# Raspi-TPUART_v1_3.net
KiCad netlist of a schematic drawn in EAGLE
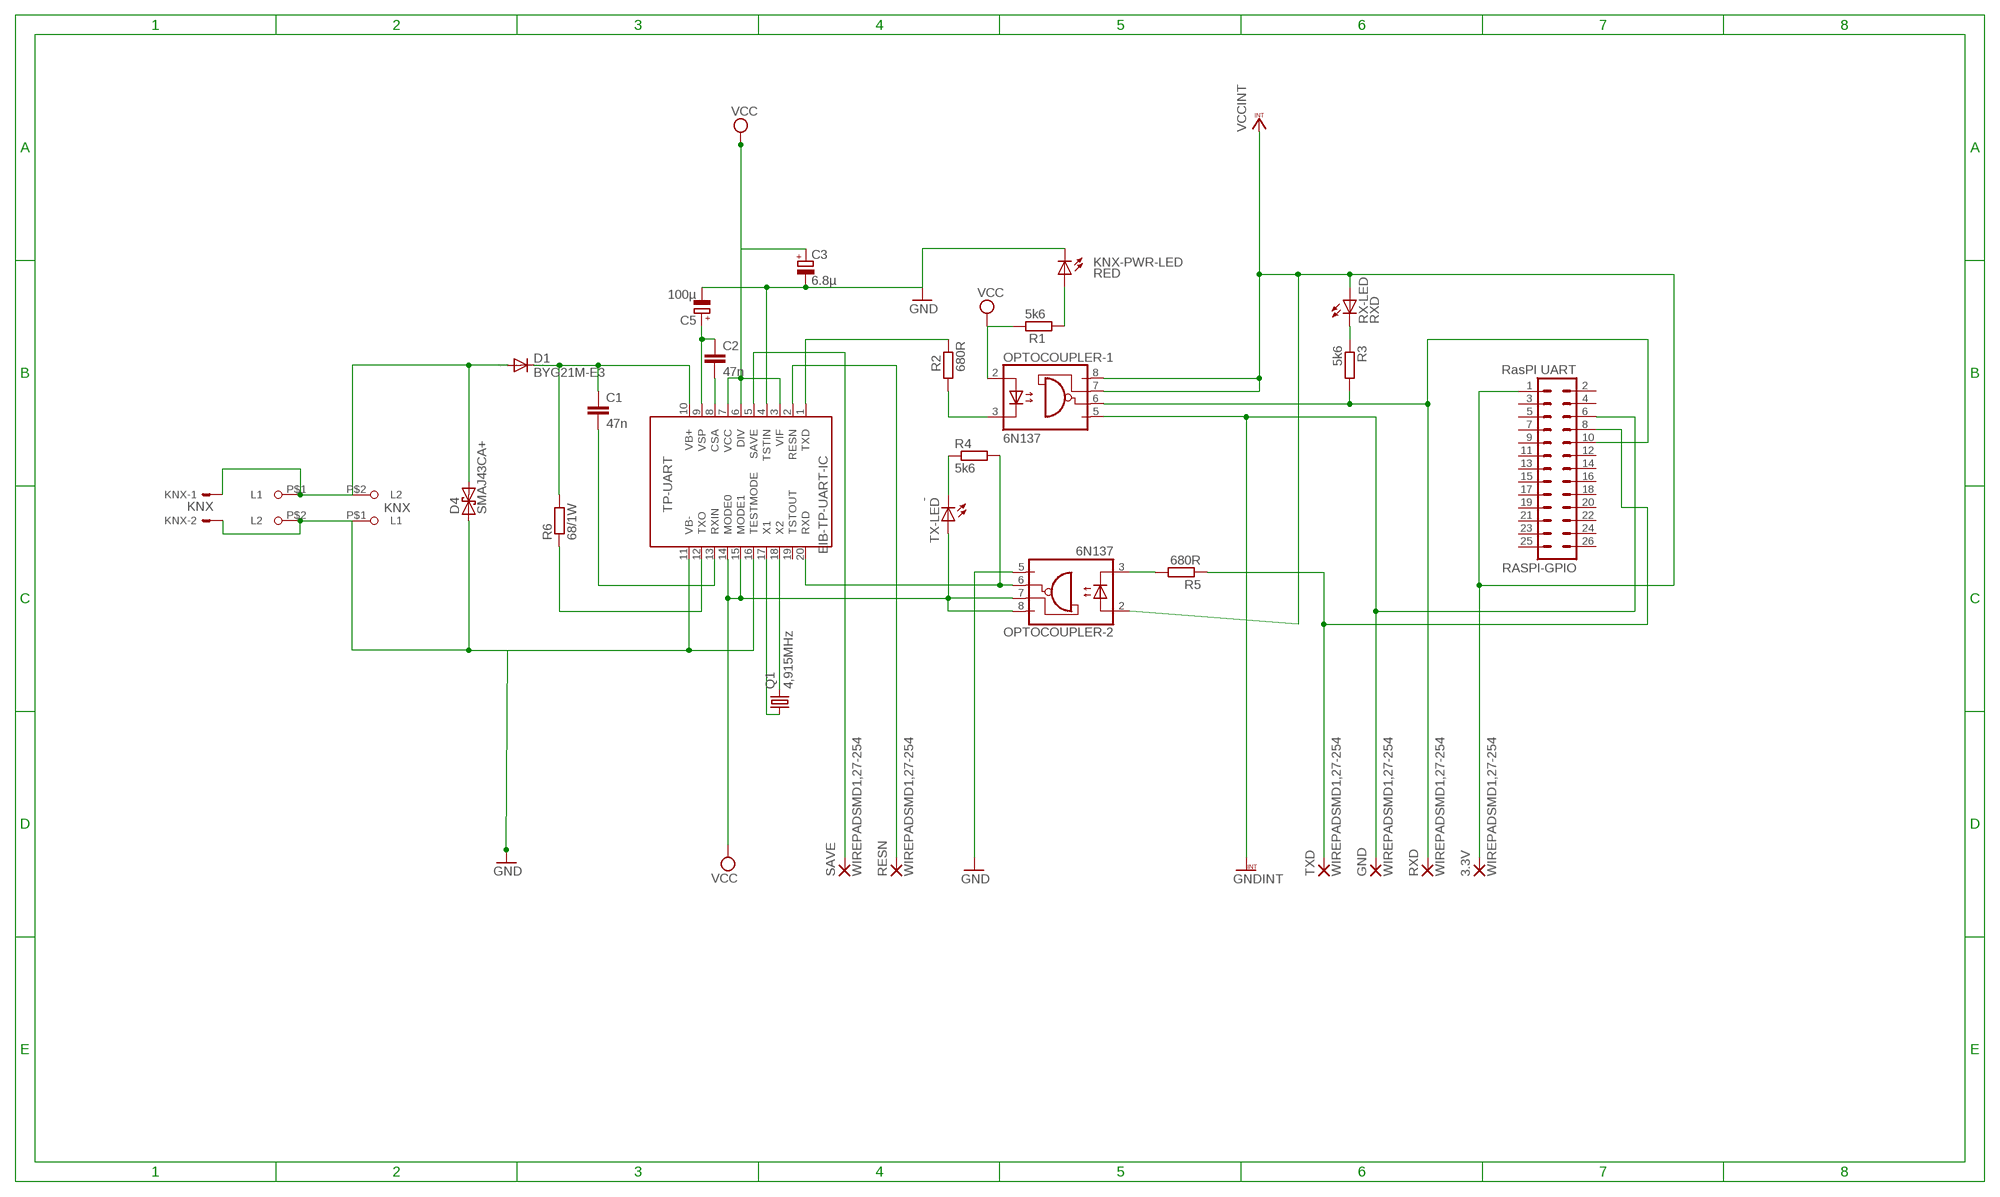
[diagram p0: schematic, sheet 1]

(export (version "E")
  (design (tool "Eeschema 10.0.6"))
  (components
    (comp (ref "3.3V")
      (value "WIREPADSMD1,27-254")
      (footprint "eagle-import:SMD1,27-2,54")
      (libsource (lib "eagle-import") (part "WIREPADSMD1,27-254"))
    )
    (comp (ref "C1")
      (value "47n")
      (footprint "eagle-import:C1206")
      (libsource (lib "eagle-import") (part "C-EUC1206"))
    )
    (comp (ref "C2")
      (value "47n")
      (footprint "eagle-import:C1206")
      (libsource (lib "eagle-import") (part "C-EUC1206"))
    )
    (comp (ref "C3")
      (value "6.8µ")
      (footprint "eagle-import:D_7343-31R")
      (libsource (lib "eagle-import") (part "CPOL-EUD/7343-31R"))
    )
    (comp (ref "C5")
      (value "100µ")
      (footprint "eagle-import:D_7343-31R")
      (libsource (lib "eagle-import") (part "CPOL-EUD/7343-31R"))
    )
    (comp (ref "D1")
      (value "BYG21M-E3")
      (footprint "eagle-import:SMB")
      (libsource (lib "eagle-import") (part "ES2D"))
    )
    (comp (ref "D4")
      (value "SMAJ43CA+")
      (footprint "eagle-import:DO214AA")
      (libsource (lib "eagle-import") (part "BZW04XXB"))
    )
    (comp (ref "EIB-TP-UART-IC")
      (value "TP-UART")
      (footprint "eagle-import:SOIC20")
      (libsource (lib "eagle-import") (part "TP-UART"))
    )
    (comp (ref "GND")
      (value "WIREPADSMD1,27-254")
      (footprint "eagle-import:SMD1,27-2,54")
      (libsource (lib "eagle-import") (part "WIREPADSMD1,27-254"))
    )
    (comp (ref "KNX")
      (value "KNX")
      (footprint "eagle-import:22-23-2021")
      (fields (field (name "MF") "MOLEX") (field (name "MPN") "22-23-2021"))
      (libsource (lib "eagle-import") (part "22-23-2021"))
    )
    (comp (ref "KNX-PWR-LED")
      (value "RED")
      (footprint "eagle-import:KA-3528ASYC")
      (libsource (lib "eagle-import") (part "LEDKA-3528ASYC"))
    )
    (comp (ref "KNX_WAGO_243")
      (value "243-211")
      (footprint "eagle-import:243-211")
      (libsource (lib "eagle-import") (part "243-211"))
    )
    (comp (ref "OPTOCOUPLER-1")
      (value "6N137")
      (footprint "eagle-import:DIL8-SMD")
      (libsource (lib "eagle-import") (part "6N137"))
    )
    (comp (ref "OPTOCOUPLER-2")
      (value "6N137")
      (footprint "eagle-import:DIL8-SMD")
      (libsource (lib "eagle-import") (part "6N137"))
    )
    (comp (ref "Q1")
      (value "4,915MHz")
      (footprint "eagle-import:HC49UP")
      (libsource (lib "eagle-import") (part "CRYSTALHC49UP"))
    )
    (comp (ref "R1")
      (value "5k6")
      (footprint "eagle-import:M1206")
      (libsource (lib "eagle-import") (part "R-EU_M1206"))
    )
    (comp (ref "R2")
      (value "680R")
      (footprint "eagle-import:M1206")
      (libsource (lib "eagle-import") (part "R-EU_M1206"))
    )
    (comp (ref "R3")
      (value "5k6")
      (footprint "eagle-import:M1206")
      (libsource (lib "eagle-import") (part "R-EU_M1206"))
    )
    (comp (ref "R4")
      (value "5k6")
      (footprint "eagle-import:M1206")
      (libsource (lib "eagle-import") (part "R-EU_M1206"))
    )
    (comp (ref "R5")
      (value "680R")
      (footprint "eagle-import:M1206")
      (libsource (lib "eagle-import") (part "R-EU_M1206"))
    )
    (comp (ref "R6")
      (value "68/1W")
      (footprint "eagle-import:R2512")
      (libsource (lib "eagle-import") (part "R-EU_R2512"))
    )
    (comp (ref "RASPI-GPIO")
      (value "RasPI UART")
      (footprint "eagle-import:MA13-2")
      (libsource (lib "eagle-import") (part "MA13-2"))
    )
    (comp (ref "RESN")
      (value "WIREPADSMD1,27-254")
      (footprint "eagle-import:SMD1,27-2,54")
      (libsource (lib "eagle-import") (part "WIREPADSMD1,27-254"))
    )
    (comp (ref "RX-LED")
      (value "RXD")
      (footprint "eagle-import:KA-3528ASYC")
      (libsource (lib "eagle-import") (part "LEDKA-3528ASYC"))
    )
    (comp (ref "RXD")
      (value "WIREPADSMD1,27-254")
      (footprint "eagle-import:SMD1,27-2,54")
      (libsource (lib "eagle-import") (part "WIREPADSMD1,27-254"))
    )
    (comp (ref "SAVE")
      (value "WIREPADSMD1,27-254")
      (footprint "eagle-import:SMD1,27-2,54")
      (libsource (lib "eagle-import") (part "WIREPADSMD1,27-254"))
    )
    (comp (ref "TX-LED")
      (value "-")
      (footprint "eagle-import:KA-3528ASYC")
      (libsource (lib "eagle-import") (part "LEDKA-3528ASYC"))
    )
    (comp (ref "TXD")
      (value "WIREPADSMD1,27-254")
      (footprint "eagle-import:SMD1,27-2,54")
      (libsource (lib "eagle-import") (part "WIREPADSMD1,27-254"))
    )
    (comp (ref "U$1")
      (value "243-211")
      (footprint "eagle-import:243-211")
      (libsource (lib "eagle-import") (part "243-211"))
    )
  )
  (nets
    (net (code "1") (name "GND") (class "Default")
      (node (ref "C3") (pin "-") (pinfunction "-_-") (pintype "passive"))
      (node (ref "C5") (pin "-") (pinfunction "-_-") (pintype "passive"))
      (node (ref "D4") (pin "A") (pinfunction "1_A") (pintype "passive"))
      (node (ref "EIB-TP-UART-IC") (pin "11") (pinfunction "VB-_11") (pintype "passive"))
      (node (ref "EIB-TP-UART-IC") (pin "16") (pinfunction "TESTMODE_16") (pintype "input"))
      (node (ref "EIB-TP-UART-IC") (pin "4") (pinfunction "TSTIN_4") (pintype "bidirectional"))
      (node (ref "KNX") (pin "2") (pinfunction "S_2") (pintype "passive"))
      (node (ref "KNX-PWR-LED") (pin "C") (pinfunction "C_C") (pintype "passive"))
      (node (ref "KNX_WAGO_243") (pin "P$1") (pinfunction "L1_P$1") (pintype "bidirectional"))
      (node (ref "OPTOCOUPLER-2") (pin "5") (pinfunction "GND_5") (pintype "passive"))
      (node (ref "U$1") (pin "P$2") (pinfunction "L2_P$2") (pintype "bidirectional"))
    )
    (net (code "2") (name "GNDINT") (class "Default")
      (node (ref "GND") (pin "1") (pinfunction "P_1") (pintype "passive"))
      (node (ref "OPTOCOUPLER-1") (pin "5") (pinfunction "GND_5") (pintype "passive"))
      (node (ref "RASPI-GPIO") (pin "6") (pinfunction "6_6") (pintype "passive"))
    )
    (net (code "3") (name "Net-(D4-2)") (class "Default")
      (node (ref "D1") (pin "A") (pinfunction "A_A") (pintype "passive"))
      (node (ref "D4") (pin "C") (pinfunction "2_C") (pintype "passive"))
      (node (ref "KNX") (pin "1") (pinfunction "S_1") (pintype "passive"))
      (node (ref "KNX_WAGO_243") (pin "P$2") (pinfunction "L2_P$2") (pintype "bidirectional"))
      (node (ref "U$1") (pin "P$1") (pinfunction "L1_P$1") (pintype "bidirectional"))
    )
    (net (code "4") (name "Net-(EIB-TP-UART-IC-CSA)") (class "Default")
      (node (ref "C2") (pin "2") (pinfunction "2_2") (pintype "passive"))
      (node (ref "EIB-TP-UART-IC") (pin "8") (pinfunction "CSA_8") (pintype "passive"))
    )
    (net (code "5") (name "Net-(EIB-TP-UART-IC-RESN)") (class "Default")
      (node (ref "EIB-TP-UART-IC") (pin "2") (pinfunction "RESN_2") (pintype "bidirectional"))
      (node (ref "RESN") (pin "1") (pinfunction "P_1") (pintype "passive"))
    )
    (net (code "6") (name "Net-(EIB-TP-UART-IC-RXD)") (class "Default")
      (node (ref "EIB-TP-UART-IC") (pin "20") (pinfunction "RXD_20") (pintype "input"))
      (node (ref "OPTOCOUPLER-2") (pin "6") (pinfunction "VO_6") (pintype "passive"))
      (node (ref "R4") (pin "2") (pinfunction "2_2") (pintype "passive"))
    )
    (net (code "7") (name "Net-(EIB-TP-UART-IC-RXIN)") (class "Default")
      (node (ref "C1") (pin "2") (pinfunction "2_2") (pintype "passive"))
      (node (ref "EIB-TP-UART-IC") (pin "13") (pinfunction "RXIN_13") (pintype "input"))
    )
    (net (code "8") (name "Net-(EIB-TP-UART-IC-SAVE)") (class "Default")
      (node (ref "EIB-TP-UART-IC") (pin "5") (pinfunction "SAVE_5") (pintype "open_collector"))
      (node (ref "SAVE") (pin "1") (pinfunction "P_1") (pintype "passive"))
    )
    (net (code "9") (name "Net-(EIB-TP-UART-IC-TXD)") (class "Default")
      (node (ref "EIB-TP-UART-IC") (pin "1") (pinfunction "TXD_1") (pintype "output"))
      (node (ref "R2") (pin "2") (pinfunction "2_2") (pintype "passive"))
    )
    (net (code "10") (name "Net-(EIB-TP-UART-IC-TXO)") (class "Default")
      (node (ref "EIB-TP-UART-IC") (pin "12") (pinfunction "TXO_12") (pintype "output"))
      (node (ref "R6") (pin "1") (pinfunction "1_1") (pintype "passive"))
    )
    (net (code "11") (name "Net-(EIB-TP-UART-IC-VB+)") (class "Default")
      (node (ref "C1") (pin "1") (pinfunction "1_1") (pintype "passive"))
      (node (ref "D1") (pin "C") (pinfunction "C_C") (pintype "passive"))
      (node (ref "EIB-TP-UART-IC") (pin "10") (pinfunction "VB+_10") (pintype "passive"))
      (node (ref "R6") (pin "2") (pinfunction "2_2") (pintype "passive"))
    )
    (net (code "12") (name "Net-(EIB-TP-UART-IC-VSP)") (class "Default")
      (node (ref "C2") (pin "1") (pinfunction "1_1") (pintype "passive"))
      (node (ref "C5") (pin "+") (pinfunction "+_+") (pintype "passive"))
      (node (ref "EIB-TP-UART-IC") (pin "9") (pinfunction "VSP_9") (pintype "passive"))
    )
    (net (code "13") (name "Net-(EIB-TP-UART-IC-X1)") (class "Default")
      (node (ref "EIB-TP-UART-IC") (pin "17") (pinfunction "X1_17") (pintype "passive"))
      (node (ref "Q1") (pin "1") (pinfunction "1_1") (pintype "passive"))
    )
    (net (code "14") (name "Net-(EIB-TP-UART-IC-X2)") (class "Default")
      (node (ref "EIB-TP-UART-IC") (pin "18") (pinfunction "X2_18") (pintype "passive"))
      (node (ref "Q1") (pin "2") (pinfunction "2_2") (pintype "passive"))
    )
    (net (code "15") (name "Net-(KNX-PWR-LED-PadA)") (class "Default")
      (node (ref "KNX-PWR-LED") (pin "A") (pinfunction "A_A") (pintype "passive"))
      (node (ref "R1") (pin "1") (pinfunction "1_1") (pintype "passive"))
    )
    (net (code "16") (name "Net-(OPTOCOUPLER-1-C)") (class "Default")
      (node (ref "OPTOCOUPLER-1") (pin "3") (pinfunction "C_3") (pintype "passive"))
      (node (ref "R2") (pin "1") (pinfunction "1_1") (pintype "passive"))
    )
    (net (code "17") (name "Net-(OPTOCOUPLER-1-VO)") (class "Default")
      (node (ref "OPTOCOUPLER-1") (pin "6") (pinfunction "VO_6") (pintype "passive"))
      (node (ref "R3") (pin "2") (pinfunction "2_2") (pintype "passive"))
      (node (ref "RASPI-GPIO") (pin "10") (pinfunction "10_10") (pintype "passive"))
      (node (ref "RXD") (pin "1") (pinfunction "P_1") (pintype "passive"))
    )
    (net (code "18") (name "Net-(OPTOCOUPLER-2-C)") (class "Default")
      (node (ref "OPTOCOUPLER-2") (pin "3") (pinfunction "C_3") (pintype "passive"))
      (node (ref "R5") (pin "2") (pinfunction "2_2") (pintype "passive"))
    )
    (net (code "19") (name "Net-(R3-Pad1)") (class "Default")
      (node (ref "R3") (pin "1") (pinfunction "1_1") (pintype "passive"))
      (node (ref "RX-LED") (pin "C") (pinfunction "C_C") (pintype "passive"))
    )
    (net (code "20") (name "Net-(R4-Pad1)") (class "Default")
      (node (ref "R4") (pin "1") (pinfunction "1_1") (pintype "passive"))
      (node (ref "TX-LED") (pin "C") (pinfunction "C_C") (pintype "passive"))
    )
    (net (code "21") (name "Net-(TXD-P)") (class "Default")
      (node (ref "R5") (pin "1") (pinfunction "1_1") (pintype "passive"))
      (node (ref "RASPI-GPIO") (pin "8") (pinfunction "8_8") (pintype "passive"))
      (node (ref "TXD") (pin "1") (pinfunction "P_1") (pintype "passive"))
    )
    (net (code "22") (name "VCC") (class "Default")
      (node (ref "C3") (pin "+") (pinfunction "+_+") (pintype "passive"))
      (node (ref "EIB-TP-UART-IC") (pin "14") (pinfunction "MODE0_14") (pintype "input"))
      (node (ref "EIB-TP-UART-IC") (pin "15") (pinfunction "MODE1_15") (pintype "input"))
      (node (ref "EIB-TP-UART-IC") (pin "3") (pinfunction "VIF_3") (pintype "input"))
      (node (ref "EIB-TP-UART-IC") (pin "6") (pinfunction "DIV_6") (pintype "input"))
      (node (ref "EIB-TP-UART-IC") (pin "7") (pinfunction "VCC_7") (pintype "output"))
      (node (ref "OPTOCOUPLER-1") (pin "2") (pinfunction "A_2") (pintype "passive"))
      (node (ref "OPTOCOUPLER-2") (pin "7") (pinfunction "VE_7") (pintype "passive"))
      (node (ref "OPTOCOUPLER-2") (pin "8") (pinfunction "VCC_8") (pintype "passive"))
      (node (ref "R1") (pin "2") (pinfunction "2_2") (pintype "passive"))
      (node (ref "TX-LED") (pin "A") (pinfunction "A_A") (pintype "passive"))
    )
    (net (code "23") (name "VCCINT") (class "Default")
      (node (ref "3.3V") (pin "1") (pinfunction "P_1") (pintype "passive"))
      (node (ref "OPTOCOUPLER-1") (pin "7") (pinfunction "VE_7") (pintype "passive"))
      (node (ref "OPTOCOUPLER-1") (pin "8") (pinfunction "VCC_8") (pintype "passive"))
      (node (ref "OPTOCOUPLER-2") (pin "2") (pinfunction "A_2") (pintype "passive"))
      (node (ref "RASPI-GPIO") (pin "1") (pinfunction "1_1") (pintype "passive"))
      (node (ref "RX-LED") (pin "A") (pinfunction "A_A") (pintype "passive"))
    )
    (net (code "24") (name "unconnected-(EIB-TP-UART-IC-TSTOUT-Pad19)") (class "Default")
      (node (ref "EIB-TP-UART-IC") (pin "19") (pinfunction "TSTOUT_19") (pintype "output"))
    )
    (net (code "25") (name "unconnected-(RASPI-GPIO-Pad2)") (class "Default")
      (node (ref "RASPI-GPIO") (pin "2") (pinfunction "2_2") (pintype "passive"))
    )
    (net (code "26") (name "unconnected-(RASPI-GPIO-Pad3)") (class "Default")
      (node (ref "RASPI-GPIO") (pin "3") (pinfunction "3_3") (pintype "passive"))
    )
    (net (code "27") (name "unconnected-(RASPI-GPIO-Pad4)") (class "Default")
      (node (ref "RASPI-GPIO") (pin "4") (pinfunction "4_4") (pintype "passive"))
    )
    (net (code "28") (name "unconnected-(RASPI-GPIO-Pad5)") (class "Default")
      (node (ref "RASPI-GPIO") (pin "5") (pinfunction "5_5") (pintype "passive"))
    )
    (net (code "29") (name "unconnected-(RASPI-GPIO-Pad7)") (class "Default")
      (node (ref "RASPI-GPIO") (pin "7") (pinfunction "7_7") (pintype "passive"))
    )
    (net (code "30") (name "unconnected-(RASPI-GPIO-Pad9)") (class "Default")
      (node (ref "RASPI-GPIO") (pin "9") (pinfunction "9_9") (pintype "passive"))
    )
    (net (code "31") (name "unconnected-(RASPI-GPIO-Pad11)") (class "Default")
      (node (ref "RASPI-GPIO") (pin "11") (pinfunction "11_11") (pintype "passive"))
    )
    (net (code "32") (name "unconnected-(RASPI-GPIO-Pad12)") (class "Default")
      (node (ref "RASPI-GPIO") (pin "12") (pinfunction "12_12") (pintype "passive"))
    )
    (net (code "33") (name "unconnected-(RASPI-GPIO-Pad13)") (class "Default")
      (node (ref "RASPI-GPIO") (pin "13") (pinfunction "13_13") (pintype "passive"))
    )
    (net (code "34") (name "unconnected-(RASPI-GPIO-Pad14)") (class "Default")
      (node (ref "RASPI-GPIO") (pin "14") (pinfunction "14_14") (pintype "passive"))
    )
    (net (code "35") (name "unconnected-(RASPI-GPIO-Pad15)") (class "Default")
      (node (ref "RASPI-GPIO") (pin "15") (pinfunction "15_15") (pintype "passive"))
    )
    (net (code "36") (name "unconnected-(RASPI-GPIO-Pad16)") (class "Default")
      (node (ref "RASPI-GPIO") (pin "16") (pinfunction "16_16") (pintype "passive"))
    )
    (net (code "37") (name "unconnected-(RASPI-GPIO-Pad17)") (class "Default")
      (node (ref "RASPI-GPIO") (pin "17") (pinfunction "17_17") (pintype "passive"))
    )
    (net (code "38") (name "unconnected-(RASPI-GPIO-Pad18)") (class "Default")
      (node (ref "RASPI-GPIO") (pin "18") (pinfunction "18_18") (pintype "passive"))
    )
    (net (code "39") (name "unconnected-(RASPI-GPIO-Pad19)") (class "Default")
      (node (ref "RASPI-GPIO") (pin "19") (pinfunction "19_19") (pintype "passive"))
    )
    (net (code "40") (name "unconnected-(RASPI-GPIO-Pad20)") (class "Default")
      (node (ref "RASPI-GPIO") (pin "20") (pinfunction "20_20") (pintype "passive"))
    )
    (net (code "41") (name "unconnected-(RASPI-GPIO-Pad21)") (class "Default")
      (node (ref "RASPI-GPIO") (pin "21") (pinfunction "21_21") (pintype "passive"))
    )
    (net (code "42") (name "unconnected-(RASPI-GPIO-Pad22)") (class "Default")
      (node (ref "RASPI-GPIO") (pin "22") (pinfunction "22_22") (pintype "passive"))
    )
    (net (code "43") (name "unconnected-(RASPI-GPIO-Pad23)") (class "Default")
      (node (ref "RASPI-GPIO") (pin "23") (pinfunction "23_23") (pintype "passive"))
    )
    (net (code "44") (name "unconnected-(RASPI-GPIO-Pad24)") (class "Default")
      (node (ref "RASPI-GPIO") (pin "24") (pinfunction "24_24") (pintype "passive"))
    )
    (net (code "45") (name "unconnected-(RASPI-GPIO-Pad25)") (class "Default")
      (node (ref "RASPI-GPIO") (pin "25") (pinfunction "25_25") (pintype "passive"))
    )
    (net (code "46") (name "unconnected-(RASPI-GPIO-Pad26)") (class "Default")
      (node (ref "RASPI-GPIO") (pin "26") (pinfunction "26_26") (pintype "passive"))
    )
  )
)
